# receiver.net
KiCad netlist of a schematic drawn in EAGLE
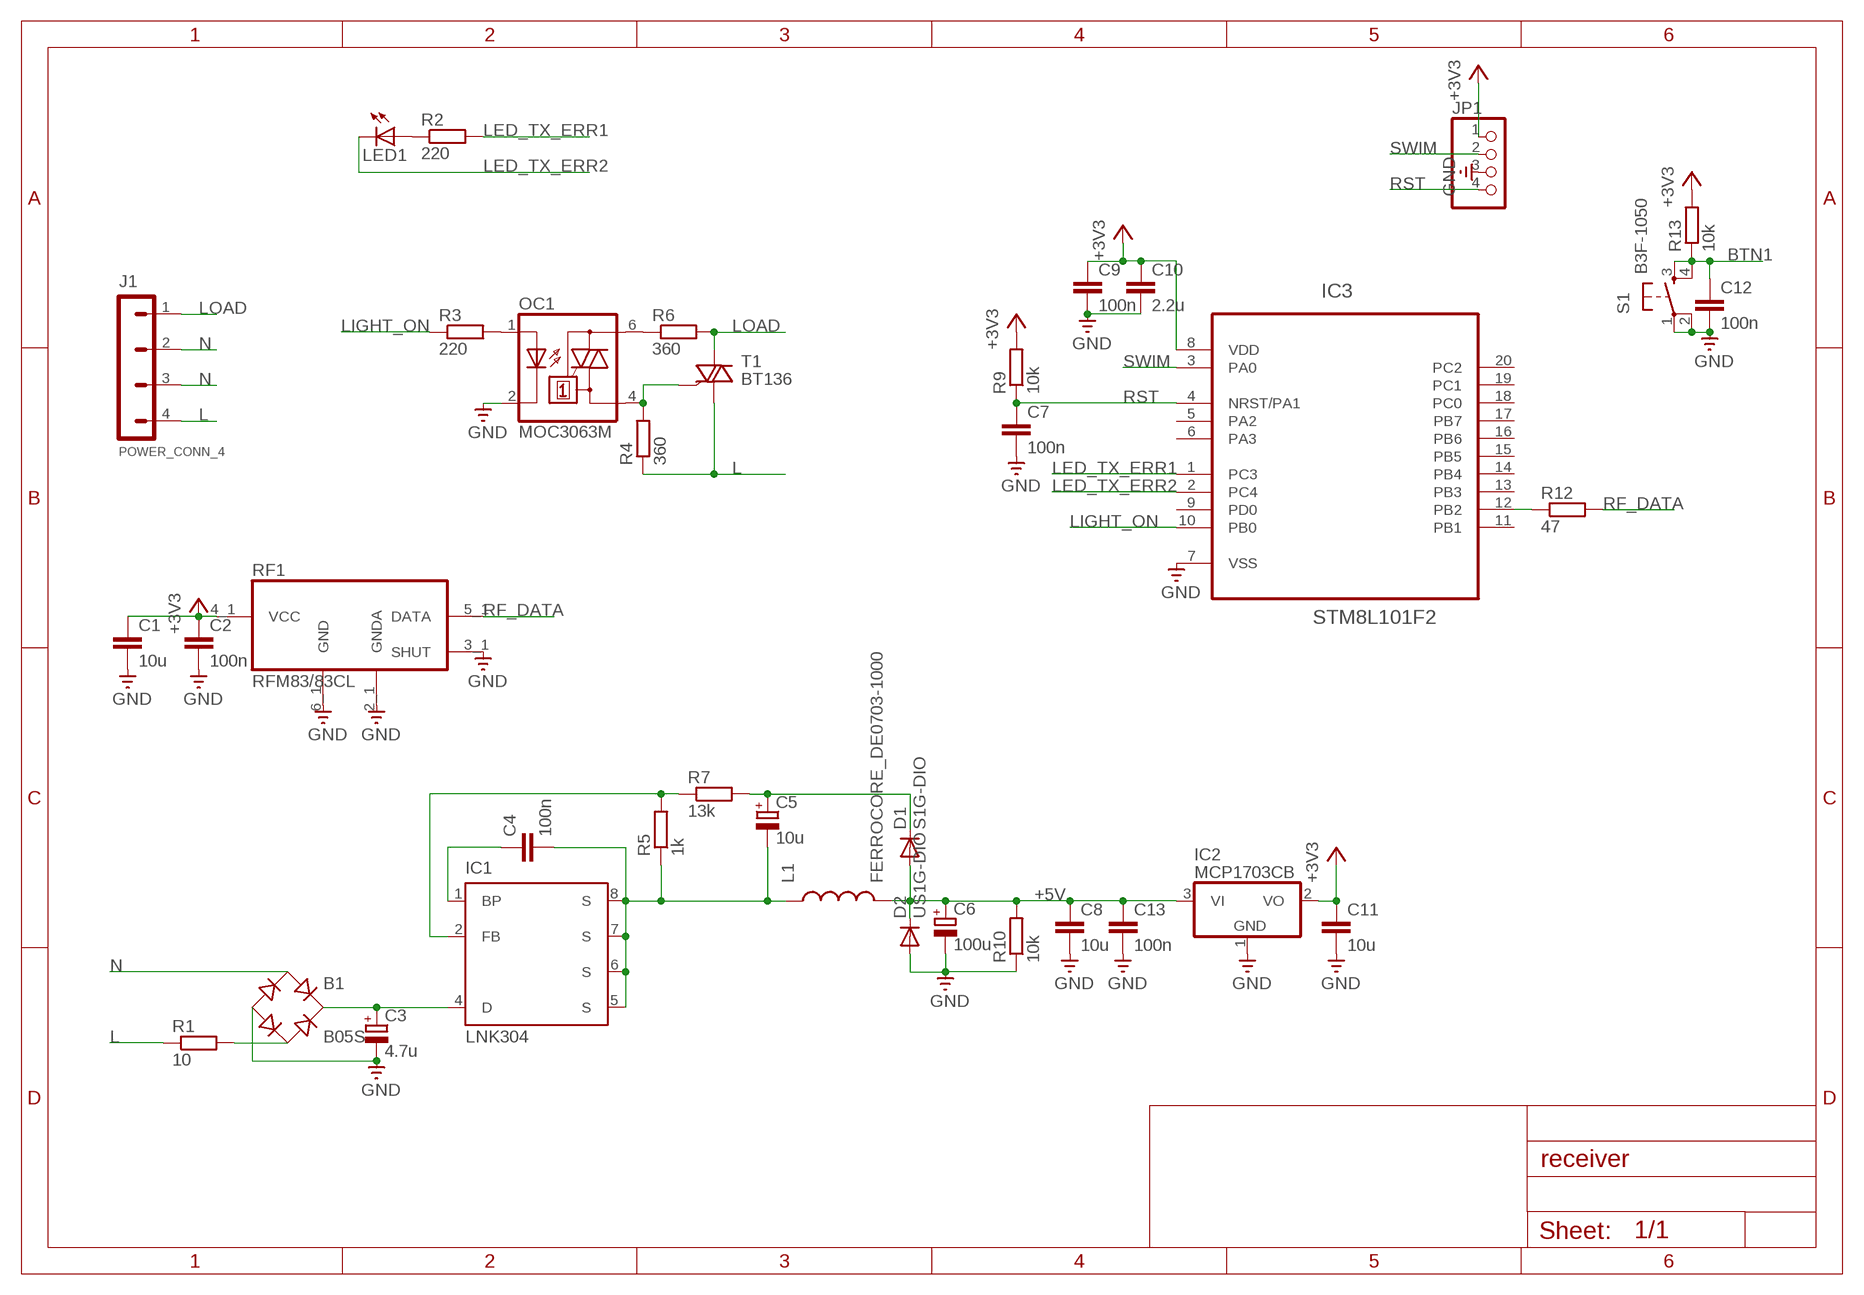
[diagram p0: schematic, sheet 1]

(export (version "E")
  (design (tool "Eeschema 10.0.6"))
  (components
    (comp (ref "B1")
      (value "B05S")
      (footprint "eagle-import:MBS")
      (libsource (lib "eagle-import") (part "BS05"))
    )
    (comp (ref "C1")
      (value "10u")
      (footprint "eagle-import:C0805K")
      (libsource (lib "eagle-import") (part "C-EUC0805K"))
    )
    (comp (ref "C2")
      (value "100n")
      (footprint "eagle-import:C0603K")
      (libsource (lib "eagle-import") (part "C-EUC0603K"))
    )
    (comp (ref "C3")
      (value "4.7u")
      (footprint "eagle-import:E5-10,5")
      (libsource (lib "eagle-import") (part "CPOL-EUE5-10.5"))
    )
    (comp (ref "C4")
      (value "100n")
      (footprint "eagle-import:C0603K")
      (libsource (lib "eagle-import") (part "C-EUC0603K"))
    )
    (comp (ref "C5")
      (value "10u")
      (footprint "eagle-import:PANASONIC_C")
      (libsource (lib "eagle-import") (part "CPOL-EUC"))
    )
    (comp (ref "C6")
      (value "100u")
      (footprint "eagle-import:PANASONIC_D")
      (libsource (lib "eagle-import") (part "CPOL-EUD"))
    )
    (comp (ref "C7")
      (value "100n")
      (footprint "eagle-import:C0603K")
      (libsource (lib "eagle-import") (part "C-EUC0603K"))
    )
    (comp (ref "C8")
      (value "10u")
      (footprint "eagle-import:C0805K")
      (libsource (lib "eagle-import") (part "C-EUC0805K"))
    )
    (comp (ref "C9")
      (value "100n")
      (footprint "eagle-import:C0603K")
      (libsource (lib "eagle-import") (part "C-EUC0603K"))
    )
    (comp (ref "C10")
      (value "2.2u")
      (footprint "eagle-import:C0805K")
      (libsource (lib "eagle-import") (part "C-EUC0805K"))
    )
    (comp (ref "C11")
      (value "10u")
      (footprint "eagle-import:C0805K")
      (libsource (lib "eagle-import") (part "C-EUC0805K"))
    )
    (comp (ref "C12")
      (value "100n")
      (footprint "eagle-import:C0603K")
      (libsource (lib "eagle-import") (part "C-EUC0603K"))
    )
    (comp (ref "C13")
      (value "100n")
      (footprint "eagle-import:C0603K")
      (libsource (lib "eagle-import") (part "C-EUC0603K"))
    )
    (comp (ref "D1")
      (value "S1G-DIO")
      (footprint "eagle-import:DO214-AC")
      (libsource (lib "eagle-import") (part "S1G-DIO"))
    )
    (comp (ref "D2")
      (value "US1G-DIO")
      (footprint "eagle-import:DO214-AC")
      (libsource (lib "eagle-import") (part "US1G-DIO"))
    )
    (comp (ref "IC1")
      (value "LNK304")
      (footprint "eagle-import:SO8_NO_PIN3")
      (libsource (lib "eagle-import") (part "LNK304"))
    )
    (comp (ref "IC2")
      (value "MCP1703CB")
      (footprint "eagle-import:SOT23")
      (libsource (lib "eagle-import") (part "MCP1703CB"))
    )
    (comp (ref "IC3")
      (value "STM8L101F2")
      (footprint "eagle-import:TSSOP20")
      (libsource (lib "eagle-import") (part "STM8L101F2"))
    )
    (comp (ref "J1")
      (value "POWER_CONN_4")
      (footprint "eagle-import:TERMINAL_BLOCK_4")
      (libsource (lib "eagle-import") (part "POWER_CONN_4"))
    )
    (comp (ref "JP1")
      (value "PINHD-1X4")
      (footprint "eagle-import:1X04")
      (libsource (lib "eagle-import") (part "PINHD-1X4"))
    )
    (comp (ref "L1")
      (value "FERROCORE_DE0703-1000")
      (footprint "eagle-import:DE0703")
      (libsource (lib "eagle-import") (part "FERROCORE_DE0703-1000"))
    )
    (comp (ref "LED1")
      (value "LED3MM")
      (footprint "eagle-import:LED3MM")
      (libsource (lib "eagle-import") (part "LED3MM"))
    )
    (comp (ref "OC1")
      (value "MOC3063M")
      (footprint "eagle-import:DIL06")
      (fields (field (name "MF") "FAIRCHILD SEMICONDUCTOR") (field (name "MPN") "MOC3023-M"))
      (libsource (lib "eagle-import") (part "MOC30M23"))
    )
    (comp (ref "R1")
      (value "10")
      (footprint "eagle-import:0309_10")
      (libsource (lib "eagle-import") (part "R-EU_0309/10"))
    )
    (comp (ref "R2")
      (value "220")
      (footprint "eagle-import:R0603")
      (libsource (lib "eagle-import") (part "R-EU_R0603"))
    )
    (comp (ref "R3")
      (value "220")
      (footprint "eagle-import:R0603")
      (libsource (lib "eagle-import") (part "R-EU_R0603"))
    )
    (comp (ref "R4")
      (value "360")
      (footprint "eagle-import:R0805")
      (libsource (lib "eagle-import") (part "R-EU_R0805"))
    )
    (comp (ref "R5")
      (value "1k")
      (footprint "eagle-import:R0603")
      (libsource (lib "eagle-import") (part "R-EU_R0603"))
    )
    (comp (ref "R6")
      (value "360")
      (footprint "eagle-import:R0805")
      (libsource (lib "eagle-import") (part "R-EU_R0805"))
    )
    (comp (ref "R7")
      (value "13k")
      (footprint "eagle-import:R0603")
      (libsource (lib "eagle-import") (part "R-EU_R0603"))
    )
    (comp (ref "R9")
      (value "10k")
      (footprint "eagle-import:R0603")
      (libsource (lib "eagle-import") (part "R-EU_R0603"))
    )
    (comp (ref "R10")
      (value "10k")
      (footprint "eagle-import:R0603")
      (libsource (lib "eagle-import") (part "R-EU_R0603"))
    )
    (comp (ref "R12")
      (value "47")
      (footprint "eagle-import:R0603")
      (libsource (lib "eagle-import") (part "R-EU_R0603"))
    )
    (comp (ref "R13")
      (value "10k")
      (footprint "eagle-import:R0603")
      (libsource (lib "eagle-import") (part "R-EU_R0603"))
    )
    (comp (ref "RF1")
      (value "RFM83/83CL")
      (footprint "eagle-import:RFM83C_83CL_CONN")
      (libsource (lib "eagle-import") (part "RFM83/83CL"))
    )
    (comp (ref "S1")
      (value "B3F-1050")
      (footprint "eagle-import:DTS-6")
      (libsource (lib "eagle-import") (part "DTS-6"))
    )
    (comp (ref "T1")
      (value "BT136")
      (footprint "eagle-import:TO220AB")
      (libsource (lib "eagle-import") (part "BT136"))
    )
  )
  (nets
    (net (code "1") (name "+3V3") (class "Default")
      (node (ref "C1") (pin "1") (pinfunction "1_1") (pintype "passive"))
      (node (ref "C10") (pin "1") (pinfunction "1_1") (pintype "passive"))
      (node (ref "C11") (pin "1") (pinfunction "1_1") (pintype "passive"))
      (node (ref "C2") (pin "1") (pinfunction "1_1") (pintype "passive"))
      (node (ref "C9") (pin "1") (pinfunction "1_1") (pintype "passive"))
      (node (ref "IC2") (pin "2") (pinfunction "VO_2") (pintype "passive"))
      (node (ref "IC3") (pin "8") (pinfunction "VDD_8") (pintype "power_in"))
      (node (ref "JP1") (pin "1") (pinfunction "1_1") (pintype "passive"))
      (node (ref "R13") (pin "2") (pinfunction "2_2") (pintype "passive"))
      (node (ref "R9") (pin "2") (pinfunction "2_2") (pintype "passive"))
      (node (ref "RF1") (pin "4_1") (pinfunction "VCC_4_1") (pintype "power_in"))
    )
    (net (code "2") (name "/+5V") (class "Default")
      (node (ref "C13") (pin "1") (pinfunction "1_1") (pintype "passive"))
      (node (ref "C6") (pin "+") (pinfunction "+_+") (pintype "passive"))
      (node (ref "C8") (pin "1") (pinfunction "1_1") (pintype "passive"))
      (node (ref "D1") (pin "A") (pinfunction "A_A") (pintype "passive"))
      (node (ref "D2") (pin "C") (pinfunction "C_C") (pintype "passive"))
      (node (ref "IC2") (pin "3") (pinfunction "VI_3") (pintype "input"))
      (node (ref "L1") (pin "P$2") (pinfunction "2_P$2") (pintype "passive"))
      (node (ref "R10") (pin "2") (pinfunction "2_2") (pintype "passive"))
    )
    (net (code "3") (name "/BTN1") (class "Default")
      (node (ref "C12") (pin "1") (pinfunction "1_1") (pintype "passive"))
      (node (ref "R13") (pin "1") (pinfunction "1_1") (pintype "passive"))
      (node (ref "S1") (pin "3") (pinfunction "3_3") (pintype "passive"))
      (node (ref "S1") (pin "4") (pinfunction "4_4") (pintype "passive"))
    )
    (net (code "4") (name "/L") (class "Default")
      (node (ref "J1") (pin "4") (pinfunction "P$4_4") (pintype "bidirectional"))
      (node (ref "R1") (pin "1") (pinfunction "1_1") (pintype "passive"))
      (node (ref "R4") (pin "1") (pinfunction "1_1") (pintype "passive"))
      (node (ref "T1") (pin "1") (pinfunction "A1_1") (pintype "passive"))
    )
    (net (code "5") (name "/LED_TX_ERR1") (class "Default")
      (node (ref "IC3") (pin "1") (pinfunction "PC3_1") (pintype "bidirectional"))
      (node (ref "R2") (pin "2") (pinfunction "2_2") (pintype "passive"))
    )
    (net (code "6") (name "/LED_TX_ERR2") (class "Default")
      (node (ref "IC3") (pin "2") (pinfunction "PC4_2") (pintype "bidirectional"))
      (node (ref "LED1") (pin "K") (pinfunction "C_K") (pintype "passive"))
    )
    (net (code "7") (name "/LIGHT_ON") (class "Default")
      (node (ref "IC3") (pin "10") (pinfunction "PB0_10") (pintype "bidirectional"))
      (node (ref "R3") (pin "1") (pinfunction "1_1") (pintype "passive"))
    )
    (net (code "8") (name "/LOAD") (class "Default")
      (node (ref "J1") (pin "1") (pinfunction "P$1_1") (pintype "bidirectional"))
      (node (ref "R6") (pin "2") (pinfunction "2_2") (pintype "passive"))
      (node (ref "T1") (pin "2") (pinfunction "A2_2") (pintype "passive"))
    )
    (net (code "9") (name "/N") (class "Default")
      (node (ref "B1") (pin "AC1") (pinfunction "AC1_AC1") (pintype "passive"))
      (node (ref "J1") (pin "2") (pinfunction "P$2_2") (pintype "bidirectional"))
      (node (ref "J1") (pin "3") (pinfunction "P$3_3") (pintype "bidirectional"))
    )
    (net (code "10") (name "/RF_DATA") (class "Default")
      (node (ref "R12") (pin "2") (pinfunction "2_2") (pintype "passive"))
      (node (ref "RF1") (pin "5_1") (pinfunction "DATA_5_1") (pintype "output"))
    )
    (net (code "11") (name "/RST") (class "Default")
      (node (ref "C7") (pin "1") (pinfunction "1_1") (pintype "passive"))
      (node (ref "IC3") (pin "4") (pinfunction "NRST/PA1_4") (pintype "bidirectional"))
      (node (ref "JP1") (pin "4") (pinfunction "4_4") (pintype "passive"))
      (node (ref "R9") (pin "1") (pinfunction "1_1") (pintype "passive"))
    )
    (net (code "12") (name "/SWIM") (class "Default")
      (node (ref "IC3") (pin "3") (pinfunction "PA0_3") (pintype "power_in"))
      (node (ref "JP1") (pin "2") (pinfunction "2_2") (pintype "passive"))
    )
    (net (code "13") (name "GND") (class "Default")
      (node (ref "B1") (pin "-") (pinfunction "-_-") (pintype "passive"))
      (node (ref "C1") (pin "2") (pinfunction "2_2") (pintype "passive"))
      (node (ref "C10") (pin "2") (pinfunction "2_2") (pintype "passive"))
      (node (ref "C11") (pin "2") (pinfunction "2_2") (pintype "passive"))
      (node (ref "C12") (pin "2") (pinfunction "2_2") (pintype "passive"))
      (node (ref "C13") (pin "2") (pinfunction "2_2") (pintype "passive"))
      (node (ref "C2") (pin "2") (pinfunction "2_2") (pintype "passive"))
      (node (ref "C3") (pin "-") (pinfunction "-_-") (pintype "passive"))
      (node (ref "C6") (pin "-") (pinfunction "-_-") (pintype "passive"))
      (node (ref "C7") (pin "2") (pinfunction "2_2") (pintype "passive"))
      (node (ref "C8") (pin "2") (pinfunction "2_2") (pintype "passive"))
      (node (ref "C9") (pin "2") (pinfunction "2_2") (pintype "passive"))
      (node (ref "D2") (pin "A") (pinfunction "A_A") (pintype "passive"))
      (node (ref "IC2") (pin "1") (pinfunction "GND_1") (pintype "passive"))
      (node (ref "IC3") (pin "7") (pinfunction "VSS_7") (pintype "power_in"))
      (node (ref "JP1") (pin "3") (pinfunction "3_3") (pintype "passive"))
      (node (ref "OC1") (pin "2") (pinfunction "C_2") (pintype "passive"))
      (node (ref "R10") (pin "1") (pinfunction "1_1") (pintype "passive"))
      (node (ref "RF1") (pin "2_1") (pinfunction "GNDA_2_1") (pintype "power_in"))
      (node (ref "RF1") (pin "3_1") (pinfunction "SHUT_3_1") (pintype "input"))
      (node (ref "RF1") (pin "6_1") (pinfunction "GND_6_1") (pintype "power_in"))
      (node (ref "S1") (pin "1") (pinfunction "1_1") (pintype "passive"))
      (node (ref "S1") (pin "2") (pinfunction "2_2") (pintype "passive"))
    )
    (net (code "14") (name "Net-(B1-PadAC2)") (class "Default")
      (node (ref "B1") (pin "AC2") (pinfunction "AC2_AC2") (pintype "passive"))
      (node (ref "R1") (pin "2") (pinfunction "2_2") (pintype "passive"))
    )
    (net (code "15") (name "Net-(C5-Pad+)") (class "Default")
      (node (ref "C5") (pin "+") (pinfunction "+_+") (pintype "passive"))
      (node (ref "D1") (pin "C") (pinfunction "C_C") (pintype "passive"))
      (node (ref "R7") (pin "2") (pinfunction "2_2") (pintype "passive"))
    )
    (net (code "16") (name "Net-(IC1-BP)") (class "Default")
      (node (ref "C4") (pin "1") (pinfunction "1_1") (pintype "passive"))
      (node (ref "IC1") (pin "1") (pinfunction "BP_1") (pintype "power_in"))
    )
    (net (code "17") (name "Net-(IC1-D)") (class "Default")
      (node (ref "B1") (pin "+") (pinfunction "+_+") (pintype "passive"))
      (node (ref "C3") (pin "+") (pinfunction "+_+") (pintype "passive"))
      (node (ref "IC1") (pin "4") (pinfunction "D_4") (pintype "power_in"))
    )
    (net (code "18") (name "Net-(IC1-FB)") (class "Default")
      (node (ref "IC1") (pin "2") (pinfunction "FB_2") (pintype "input"))
      (node (ref "R5") (pin "2") (pinfunction "2_2") (pintype "passive"))
      (node (ref "R7") (pin "1") (pinfunction "1_1") (pintype "passive"))
    )
    (net (code "19") (name "Net-(IC3-PB2)") (class "Default")
      (node (ref "IC3") (pin "12") (pinfunction "PB2_12") (pintype "bidirectional"))
      (node (ref "R12") (pin "1") (pinfunction "1_1") (pintype "passive"))
    )
    (net (code "20") (name "Net-(L1-1)") (class "Default")
      (node (ref "C4") (pin "2") (pinfunction "2_2") (pintype "passive"))
      (node (ref "C5") (pin "-") (pinfunction "-_-") (pintype "passive"))
      (node (ref "IC1") (pin "5") (pinfunction "S_5") (pintype "power_in"))
      (node (ref "IC1") (pin "6") (pinfunction "S_6") (pintype "power_in"))
      (node (ref "IC1") (pin "7") (pinfunction "S_7") (pintype "power_in"))
      (node (ref "IC1") (pin "8") (pinfunction "S_8") (pintype "power_in"))
      (node (ref "L1") (pin "P$1") (pinfunction "1_P$1") (pintype "passive"))
      (node (ref "R5") (pin "1") (pinfunction "1_1") (pintype "passive"))
    )
    (net (code "21") (name "Net-(LED1-PadA)") (class "Default")
      (node (ref "LED1") (pin "A") (pinfunction "A_A") (pintype "passive"))
      (node (ref "R2") (pin "1") (pinfunction "1_1") (pintype "passive"))
    )
    (net (code "22") (name "Net-(OC1-A)") (class "Default")
      (node (ref "OC1") (pin "1") (pinfunction "A_1") (pintype "passive"))
      (node (ref "R3") (pin "2") (pinfunction "2_2") (pintype "passive"))
    )
    (net (code "23") (name "Net-(OC1-A1)") (class "Default")
      (node (ref "OC1") (pin "4") (pinfunction "A1_4") (pintype "passive"))
      (node (ref "R4") (pin "2") (pinfunction "2_2") (pintype "passive"))
      (node (ref "T1") (pin "3") (pinfunction "G_3") (pintype "passive"))
    )
    (net (code "24") (name "Net-(OC1-A2)") (class "Default")
      (node (ref "OC1") (pin "6") (pinfunction "A2_6") (pintype "passive"))
      (node (ref "R6") (pin "1") (pinfunction "1_1") (pintype "passive"))
    )
    (net (code "25") (name "unconnected-(IC3-PA2-Pad5)") (class "Default")
      (node (ref "IC3") (pin "5") (pinfunction "PA2_5") (pintype "bidirectional"))
    )
    (net (code "26") (name "unconnected-(IC3-PA3-Pad6)") (class "Default")
      (node (ref "IC3") (pin "6") (pinfunction "PA3_6") (pintype "bidirectional"))
    )
    (net (code "27") (name "unconnected-(IC3-PB1-Pad11)") (class "Default")
      (node (ref "IC3") (pin "11") (pinfunction "PB1_11") (pintype "bidirectional"))
    )
    (net (code "28") (name "unconnected-(IC3-PB3-Pad13)") (class "Default")
      (node (ref "IC3") (pin "13") (pinfunction "PB3_13") (pintype "bidirectional"))
    )
    (net (code "29") (name "unconnected-(IC3-PB4-Pad14)") (class "Default")
      (node (ref "IC3") (pin "14") (pinfunction "PB4_14") (pintype "bidirectional"))
    )
    (net (code "30") (name "unconnected-(IC3-PB5-Pad15)") (class "Default")
      (node (ref "IC3") (pin "15") (pinfunction "PB5_15") (pintype "bidirectional"))
    )
    (net (code "31") (name "unconnected-(IC3-PB6-Pad16)") (class "Default")
      (node (ref "IC3") (pin "16") (pinfunction "PB6_16") (pintype "bidirectional"))
    )
    (net (code "32") (name "unconnected-(IC3-PB7-Pad17)") (class "Default")
      (node (ref "IC3") (pin "17") (pinfunction "PB7_17") (pintype "bidirectional"))
    )
    (net (code "33") (name "unconnected-(IC3-PC0-Pad18)") (class "Default")
      (node (ref "IC3") (pin "18") (pinfunction "PC0_18") (pintype "bidirectional"))
    )
    (net (code "34") (name "unconnected-(IC3-PC1-Pad19)") (class "Default")
      (node (ref "IC3") (pin "19") (pinfunction "PC1_19") (pintype "bidirectional"))
    )
    (net (code "35") (name "unconnected-(IC3-PC2-Pad20)") (class "Default")
      (node (ref "IC3") (pin "20") (pinfunction "PC2_20") (pintype "bidirectional"))
    )
    (net (code "36") (name "unconnected-(IC3-PD0-Pad9)") (class "Default")
      (node (ref "IC3") (pin "9") (pinfunction "PD0_9") (pintype "bidirectional"))
    )
  )
)
